# Sensor_Probe_Panel.net
KiCad netlist of a schematic drawn in Altium Designer
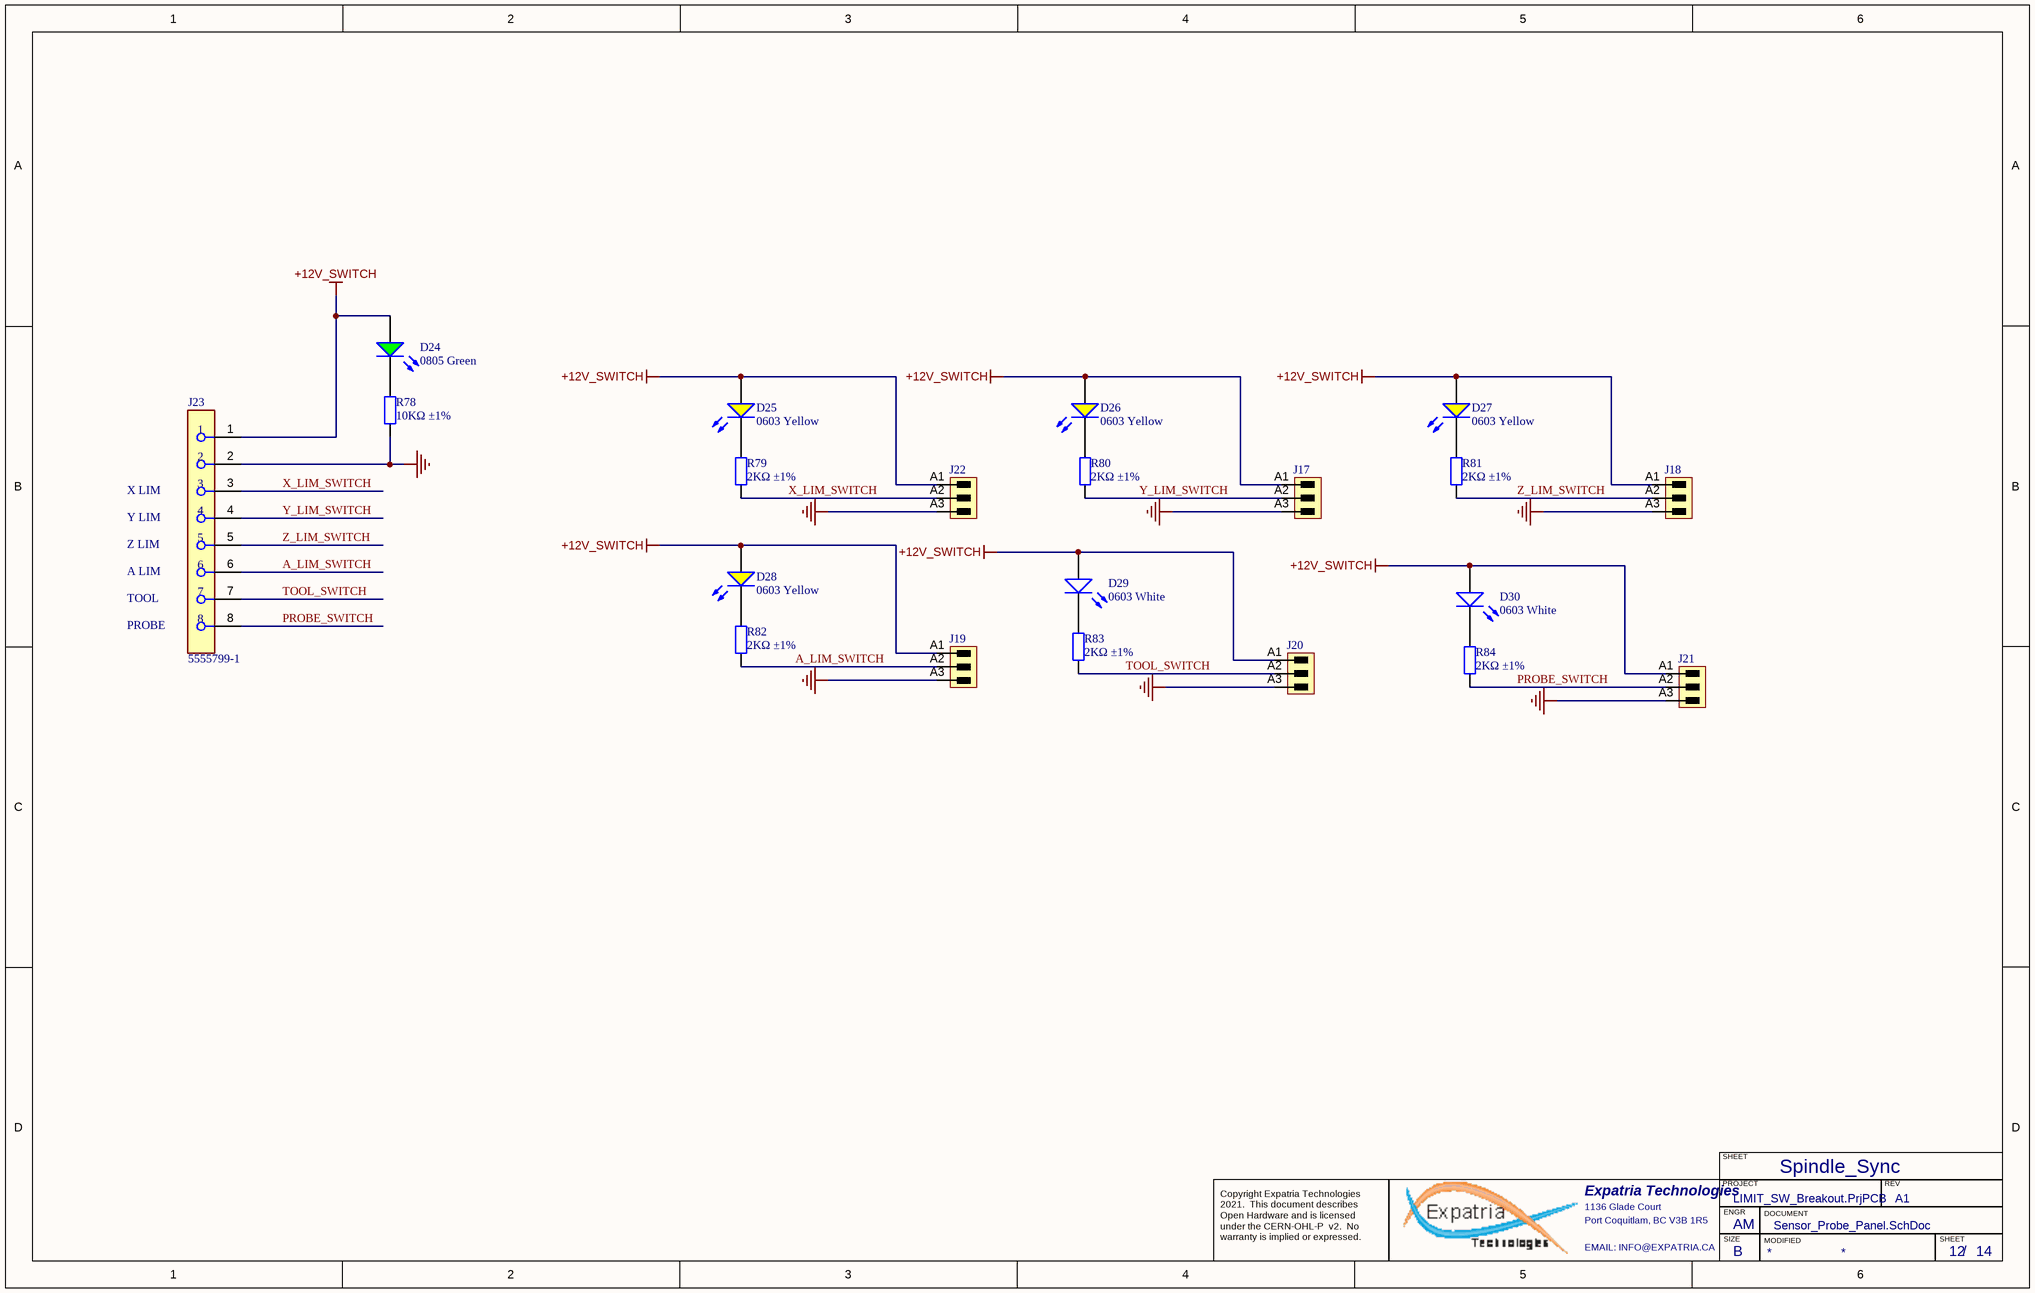
[diagram p0: Sensor_Probe_Panel.SchDoc]

(export (version "E")
  (design (tool "Eeschema 10.0.6"))
  (components
    (comp (ref "D24")
      (value "0805 Green")
      (footprint "0805_LED_S1")
      (description "LED")
      (libsource (lib "LED") (part "0805 LED Green"))
    )
    (comp (ref "D25")
      (value "0603 Yellow")
      (footprint "0603_LED_S1")
      (description "LED")
      (libsource (lib "LED") (part "0603 LED Yellow"))
    )
    (comp (ref "D26")
      (value "0603 Yellow")
      (footprint "0603_LED_S1")
      (description "LED")
      (libsource (lib "LED") (part "0603 LED Yellow"))
    )
    (comp (ref "D27")
      (value "0603 Yellow")
      (footprint "0603_LED_S1")
      (description "LED")
      (libsource (lib "LED") (part "0603 LED Yellow"))
    )
    (comp (ref "D28")
      (value "0603 Yellow")
      (footprint "0603_LED_S1")
      (description "LED")
      (libsource (lib "LED") (part "0603 LED Yellow"))
    )
    (comp (ref "D29")
      (value "0603 White")
      (footprint "0603_LED_S1")
      (description "LED")
      (libsource (lib "LED") (part "0603 LED White"))
    )
    (comp (ref "D30")
      (value "0603 White")
      (footprint "0603_LED_S1")
      (description "LED")
      (libsource (lib "LED") (part "0603 LED White"))
    )
    (comp (ref "J17")
      (value "~")
      (footprint "SL_3_50_180G_03")
      (fields
        (field (name "PARTNUMBER") "WJ15EDGVC-3.5-3P")
        (field (name "MANUFACTURER") "Ningbo Kangnex Elec")
      )
      (libsource (lib "PrintNC_GRBLHAL_Breakout") (part "Header_Male_03_1x03"))
    )
    (comp (ref "J18")
      (value "~")
      (footprint "SL_3_50_180G_03")
      (fields
        (field (name "PARTNUMBER") "WJ15EDGVC-3.5-3P")
        (field (name "MANUFACTURER") "Ningbo Kangnex Elec")
      )
      (libsource (lib "PrintNC_GRBLHAL_Breakout") (part "Header_Male_03_1x03"))
    )
    (comp (ref "J19")
      (value "~")
      (footprint "SL_3_50_180G_03")
      (fields
        (field (name "PARTNUMBER") "WJ15EDGVC-3.5-3P")
        (field (name "MANUFACTURER") "Ningbo Kangnex Elec")
      )
      (libsource (lib "PrintNC_GRBLHAL_Breakout") (part "Header_Male_03_1x03"))
    )
    (comp (ref "J20")
      (value "~")
      (footprint "SL_3_50_180G_03")
      (fields
        (field (name "PARTNUMBER") "WJ15EDGVC-3.5-3P")
        (field (name "MANUFACTURER") "Ningbo Kangnex Elec")
      )
      (libsource (lib "PrintNC_GRBLHAL_Breakout") (part "Header_Male_03_1x03"))
    )
    (comp (ref "J21")
      (value "~")
      (footprint "SL_3_50_180G_03")
      (fields
        (field (name "PARTNUMBER") "WJ15EDGVC-3.5-3P")
        (field (name "MANUFACTURER") "Ningbo Kangnex Elec")
      )
      (libsource (lib "PrintNC_GRBLHAL_Breakout") (part "Header_Male_03_1x03"))
    )
    (comp (ref "J22")
      (value "~")
      (footprint "SL_3_50_180G_03")
      (fields
        (field (name "PARTNUMBER") "WJ15EDGVC-3.5-3P")
        (field (name "MANUFACTURER") "Ningbo Kangnex Elec")
      )
      (libsource (lib "PrintNC_GRBLHAL_Breakout") (part "Header_Male_03_1x03"))
    )
    (comp (ref "J23")
      (value "5555799-1")
      (footprint "FP-5555799-1-MFG")
      (description "CONN MOD JACK 8P8C VERT UNSHLD")
      (fields
        (field (name "MANUFACTURER") "TE Connectivity")
        (field (name "OCTOPART") "https://octopart.com/5555799-1-te+connectivity-39526335")
      )
      (libsource (lib "PrintNC_GRBLHAL_Breakout") (part "a32a9c29f5c2290c50060dfb8ad7212"))
    )
    (comp (ref "R78")
      (value "10KΩ ±1%")
      (footprint "0603_R")
      (description "Chip resistor")
      (fields (field (name "MANUFACTURER") "Uniroyal Elec") (field (name "PARTNUMBER") "0603WAF1002T5E"))
      (libsource (lib "PrintNC_GRBLHAL_Breakout") (part "0603 10K (1002) 1%"))
    )
    (comp (ref "R79")
      (value "2KΩ ±1%")
      (footprint "0603_R")
      (description "Chip resistor")
      (fields (field (name "MANUFACTURER") "Uniroyal Elec") (field (name "PARTNUMBER") "0603WAF2001T5E"))
      (libsource (lib "PrintNC_GRBLHAL_Breakout") (part "0603 2K (2001) 1%"))
    )
    (comp (ref "R80")
      (value "2KΩ ±1%")
      (footprint "0603_R")
      (description "Chip resistor")
      (fields (field (name "MANUFACTURER") "Uniroyal Elec") (field (name "PARTNUMBER") "0603WAF2001T5E"))
      (libsource (lib "PrintNC_GRBLHAL_Breakout") (part "0603 2K (2001) 1%"))
    )
    (comp (ref "R81")
      (value "2KΩ ±1%")
      (footprint "0603_R")
      (description "Chip resistor")
      (fields (field (name "MANUFACTURER") "Uniroyal Elec") (field (name "PARTNUMBER") "0603WAF2001T5E"))
      (libsource (lib "PrintNC_GRBLHAL_Breakout") (part "0603 2K (2001) 1%"))
    )
    (comp (ref "R82")
      (value "2KΩ ±1%")
      (footprint "0603_R")
      (description "Chip resistor")
      (fields (field (name "MANUFACTURER") "Uniroyal Elec") (field (name "PARTNUMBER") "0603WAF2001T5E"))
      (libsource (lib "PrintNC_GRBLHAL_Breakout") (part "0603 2K (2001) 1%"))
    )
    (comp (ref "R83")
      (value "2KΩ ±1%")
      (footprint "0603_R")
      (description "Chip resistor")
      (fields (field (name "MANUFACTURER") "Uniroyal Elec") (field (name "PARTNUMBER") "0603WAF2001T5E"))
      (libsource (lib "PrintNC_GRBLHAL_Breakout") (part "0603 2K (2001) 1%"))
    )
    (comp (ref "R84")
      (value "2KΩ ±1%")
      (footprint "0603_R")
      (description "Chip resistor")
      (fields (field (name "MANUFACTURER") "Uniroyal Elec") (field (name "PARTNUMBER") "0603WAF2001T5E"))
      (libsource (lib "PrintNC_GRBLHAL_Breakout") (part "0603 2K (2001) 1%"))
    )
  )
  (nets
    (net (code "1") (name "+12V_SWITCH") (class "Default")
      (node (ref "D24") (pin "A") (pinfunction "A_A") (pintype "passive"))
      (node (ref "D25") (pin "A") (pinfunction "A_A") (pintype "passive"))
      (node (ref "D26") (pin "A") (pinfunction "A_A") (pintype "passive"))
      (node (ref "D27") (pin "A") (pinfunction "A_A") (pintype "passive"))
      (node (ref "D28") (pin "A") (pinfunction "A_A") (pintype "passive"))
      (node (ref "D29") (pin "A") (pinfunction "A_A") (pintype "passive"))
      (node (ref "D30") (pin "A") (pinfunction "A_A") (pintype "passive"))
      (node (ref "J17") (pin "A1") (pinfunction "A1_A1") (pintype "passive"))
      (node (ref "J18") (pin "A1") (pinfunction "A1_A1") (pintype "passive"))
      (node (ref "J19") (pin "A1") (pinfunction "A1_A1") (pintype "passive"))
      (node (ref "J20") (pin "A1") (pinfunction "A1_A1") (pintype "passive"))
      (node (ref "J21") (pin "A1") (pinfunction "A1_A1") (pintype "passive"))
      (node (ref "J22") (pin "A1") (pinfunction "A1_A1") (pintype "passive"))
      (node (ref "J23") (pin "1") (pinfunction "1_1") (pintype "passive"))
    )
    (net (code "2") (name "/A_LIM_SWITCH") (class "Default")
      (node (ref "J19") (pin "A2") (pinfunction "A2_A2") (pintype "passive"))
      (node (ref "J23") (pin "6") (pinfunction "6_6") (pintype "passive"))
      (node (ref "R82") (pin "2") (pinfunction "2_2") (pintype "passive"))
    )
    (net (code "3") (name "/PROBE_SWITCH") (class "Default")
      (node (ref "J21") (pin "A2") (pinfunction "A2_A2") (pintype "passive"))
      (node (ref "J23") (pin "8") (pinfunction "8_8") (pintype "passive"))
      (node (ref "R84") (pin "2") (pinfunction "2_2") (pintype "passive"))
    )
    (net (code "4") (name "/TOOL_SWITCH") (class "Default")
      (node (ref "J20") (pin "A2") (pinfunction "A2_A2") (pintype "passive"))
      (node (ref "J23") (pin "7") (pinfunction "7_7") (pintype "passive"))
      (node (ref "R83") (pin "2") (pinfunction "2_2") (pintype "passive"))
    )
    (net (code "5") (name "/X_LIM_SWITCH") (class "Default")
      (node (ref "J22") (pin "A2") (pinfunction "A2_A2") (pintype "passive"))
      (node (ref "J23") (pin "3") (pinfunction "3_3") (pintype "passive"))
      (node (ref "R79") (pin "2") (pinfunction "2_2") (pintype "passive"))
    )
    (net (code "6") (name "/Y_LIM_SWITCH") (class "Default")
      (node (ref "J17") (pin "A2") (pinfunction "A2_A2") (pintype "passive"))
      (node (ref "J23") (pin "4") (pinfunction "4_4") (pintype "passive"))
      (node (ref "R80") (pin "2") (pinfunction "2_2") (pintype "passive"))
    )
    (net (code "7") (name "/Z_LIM_SWITCH") (class "Default")
      (node (ref "J18") (pin "A2") (pinfunction "A2_A2") (pintype "passive"))
      (node (ref "J23") (pin "5") (pinfunction "5_5") (pintype "passive"))
      (node (ref "R81") (pin "2") (pinfunction "2_2") (pintype "passive"))
    )
    (net (code "8") (name "GND_SWITCH") (class "Default")
      (node (ref "J17") (pin "A3") (pinfunction "A3_A3") (pintype "passive"))
      (node (ref "J18") (pin "A3") (pinfunction "A3_A3") (pintype "passive"))
      (node (ref "J19") (pin "A3") (pinfunction "A3_A3") (pintype "passive"))
      (node (ref "J20") (pin "A3") (pinfunction "A3_A3") (pintype "passive"))
      (node (ref "J21") (pin "A3") (pinfunction "A3_A3") (pintype "passive"))
      (node (ref "J22") (pin "A3") (pinfunction "A3_A3") (pintype "passive"))
      (node (ref "J23") (pin "2") (pinfunction "2_2") (pintype "passive"))
      (node (ref "R78") (pin "1") (pinfunction "1_1") (pintype "passive"))
    )
    (net (code "9") (name "Net-(D24-PadK)") (class "Default")
      (node (ref "D24") (pin "K") (pinfunction "K_K") (pintype "passive"))
      (node (ref "R78") (pin "2") (pinfunction "2_2") (pintype "passive"))
    )
    (net (code "10") (name "Net-(D25-PadK)") (class "Default")
      (node (ref "D25") (pin "K") (pinfunction "K_K") (pintype "passive"))
      (node (ref "R79") (pin "1") (pinfunction "1_1") (pintype "passive"))
    )
    (net (code "11") (name "Net-(D26-PadK)") (class "Default")
      (node (ref "D26") (pin "K") (pinfunction "K_K") (pintype "passive"))
      (node (ref "R80") (pin "1") (pinfunction "1_1") (pintype "passive"))
    )
    (net (code "12") (name "Net-(D27-PadK)") (class "Default")
      (node (ref "D27") (pin "K") (pinfunction "K_K") (pintype "passive"))
      (node (ref "R81") (pin "1") (pinfunction "1_1") (pintype "passive"))
    )
    (net (code "13") (name "Net-(D28-PadK)") (class "Default")
      (node (ref "D28") (pin "K") (pinfunction "K_K") (pintype "passive"))
      (node (ref "R82") (pin "1") (pinfunction "1_1") (pintype "passive"))
    )
    (net (code "14") (name "Net-(D29-PadK)") (class "Default")
      (node (ref "D29") (pin "K") (pinfunction "K_K") (pintype "passive"))
      (node (ref "R83") (pin "1") (pinfunction "1_1") (pintype "passive"))
    )
    (net (code "15") (name "Net-(D30-PadK)") (class "Default")
      (node (ref "D30") (pin "K") (pinfunction "K_K") (pintype "passive"))
      (node (ref "R84") (pin "1") (pinfunction "1_1") (pintype "passive"))
    )
  )
)
